# RpiPaw1_Sch.net
KiCad netlist of a schematic drawn in Altium Designer
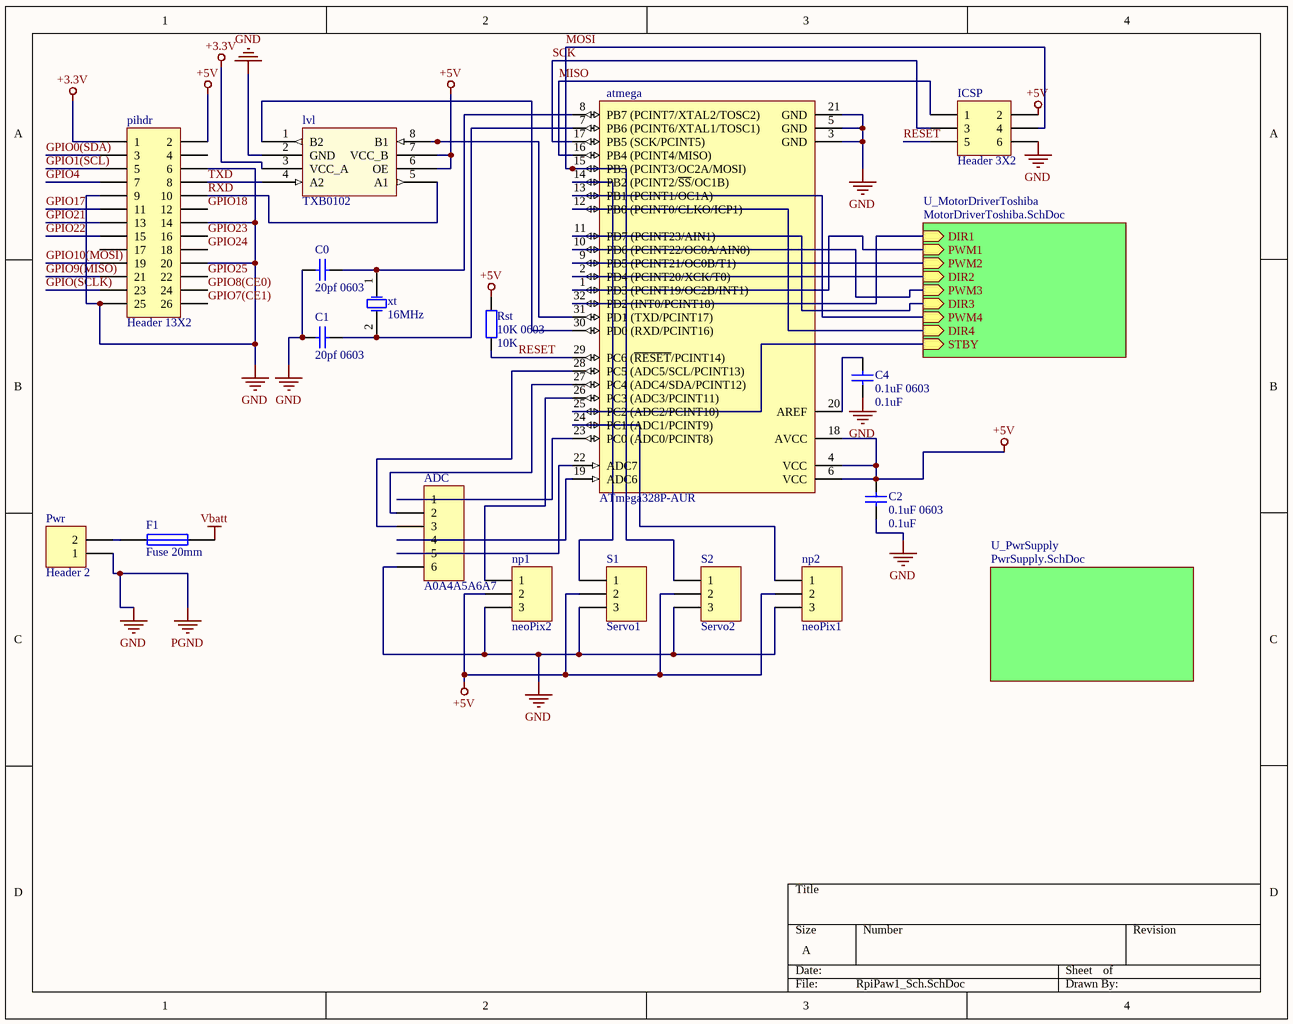
[diagram p0: RpiPaw1_Sch.SchDoc]

(export (version "E")
  (design (tool "Eeschema 10.0.6"))
  (components
    (comp (ref "ADC")
      (value "A0A4A5A6A7")
      (footprint "HDR1X6")
      (description "Header, 6-Pin")
      (fields (field (name "PUBLISHER") "Altium Limited"))
      (libsource (lib "Miscellaneous Connectors") (part "Header 6"))
    )
    (comp (ref "atmega")
      (value "ATmega328P-AUR")
      (footprint "Altera Footprints:TQFP32_N")
      (fields (field (name "PUBLISHER") "Altium Limited"))
      (libsource (lib "Atmel Microcontroller 8-Bit megaAVR") (part "ATmega328P-AUR"))
    )
    (comp (ref "C0")
      (value "20pf 0603")
      (footprint "Miscellaneous Devices:J1-0603")
      (description "Capacitor")
      (fields (field (name "PUBLISHER") "Altium Limited"))
      (libsource (lib "Miscellaneous Devices") (part "Cap"))
    )
    (comp (ref "C1")
      (value "20pf 0603")
      (footprint "Miscellaneous Devices:J1-0603")
      (description "Capacitor")
      (fields (field (name "PUBLISHER") "Altium Limited"))
      (libsource (lib "Miscellaneous Devices") (part "Cap"))
    )
    (comp (ref "C2")
      (value "0.1uF 0603")
      (footprint "Miscellaneous Devices:J1-0603")
      (description "Capacitor")
      (fields (field (name "ALTIUM_VALUE") "0.1uF") (field (name "PUBLISHER") "Altium Limited"))
      (libsource (lib "Miscellaneous Devices") (part "Cap"))
    )
    (comp (ref "C4")
      (value "0.1uF 0603")
      (footprint "J1-0603")
      (description "Capacitor")
      (fields (field (name "ALTIUM_VALUE") "0.1uF") (field (name "PUBLISHER") "Altium Limited"))
      (libsource (lib "Miscellaneous Devices") (part "Cap"))
    )
    (comp (ref "F1")
      (value "Fuse 20mm")
      (footprint "PawPcbLib1:FusePad1")
      (description "Fuse")
      (fields (field (name "PUBLISHER") "Altium Limited"))
      (libsource (lib "Miscellaneous Devices") (part "Fuse 1"))
    )
    (comp (ref "ICSP")
      (value "Header 3X2")
      (footprint "HDR2X3")
      (description "Header, 3-Pin, Dual row")
      (fields (field (name "PUBLISHER") "Altium Limited"))
      (libsource (lib "Miscellaneous Connectors") (part "Header 3X2"))
    )
    (comp (ref "lvl")
      (value "TXB0102")
      (footprint "PawPcbLib1:TSSOP50P310X90-8N")
      (description "3.3V Level translator")
      (libsource (lib "RpiPaw1_SchLib") (part "TXB0102"))
    )
    (comp (ref "np1")
      (value "neoPix2")
      (footprint "HDR1X3")
      (description "Header, 3-Pin")
      (fields (field (name "PUBLISHER") "Altium Limited"))
      (libsource (lib "Miscellaneous Connectors") (part "Header 3"))
    )
    (comp (ref "np2")
      (value "neoPix1")
      (footprint "HDR1X3")
      (description "Header, 3-Pin")
      (fields (field (name "PUBLISHER") "Altium Limited"))
      (libsource (lib "Miscellaneous Connectors") (part "Header 3"))
    )
    (comp (ref "pihdr")
      (value "Header 13X2")
      (footprint "HDR2X13")
      (description "Header, 13-Pin, Dual row")
      (fields (field (name "PUBLISHER") "Altium Limited"))
      (libsource (lib "Miscellaneous Connectors") (part "Header 13X2"))
    )
    (comp (ref "Pwr")
      (value "Header 2")
      (footprint "PawPcbLib1:PwrPlug1")
      (description "Header, 2-Pin")
      (fields (field (name "PUBLISHER") "Altium Limited"))
      (libsource (lib "Miscellaneous Connectors") (part "Header 2"))
    )
    (comp (ref "Rst")
      (value "10K 0603")
      (footprint "J1-0603")
      (description "Resistor")
      (fields (field (name "ALTIUM_VALUE") "10K") (field (name "PUBLISHER") "Altium Limited"))
      (libsource (lib "Miscellaneous Devices") (part "Res2"))
    )
    (comp (ref "S1")
      (value "Servo1")
      (footprint "HDR1X3")
      (description "Header, 3-Pin")
      (fields (field (name "PUBLISHER") "Altium Limited"))
      (libsource (lib "Miscellaneous Connectors") (part "Header 3"))
    )
    (comp (ref "S2")
      (value "Servo2")
      (footprint "HDR1X3")
      (description "Header, 3-Pin")
      (fields (field (name "PUBLISHER") "Altium Limited"))
      (libsource (lib "Miscellaneous Connectors") (part "Header 3"))
    )
    (comp (ref "xt")
      (value "16MHz")
      (footprint "Axial 0.2")
      (description "Crystal Oscillator")
      (fields (field (name "PUBLISHER") "Altium Limited"))
      (libsource (lib "Miscellaneous Devices") (part "XTAL"))
    )
  )
  (nets
    (net (code "1") (name "+3.3V") (class "Default")
      (node (ref "lvl") (pin "3") (pinfunction "VCC_A_3") (pintype "power_in"))
      (node (ref "pihdr") (pin "1") (pinfunction "1_1") (pintype "passive"))
    )
    (net (code "2") (name "+5V") (class "Default")
      (node (ref "C2") (pin "2") (pinfunction "2_2") (pintype "passive"))
      (node (ref "ICSP") (pin "2") (pinfunction "2_2") (pintype "passive"))
      (node (ref "Rst") (pin "2") (pinfunction "2_2") (pintype "passive"))
      (node (ref "S1") (pin "2") (pinfunction "2_2") (pintype "passive"))
      (node (ref "S2") (pin "2") (pinfunction "2_2") (pintype "passive"))
      (node (ref "atmega") (pin "18") (pinfunction "AVCC_18") (pintype "power_in"))
      (node (ref "atmega") (pin "4") (pinfunction "VCC_4") (pintype "power_in"))
      (node (ref "atmega") (pin "6") (pinfunction "VCC_6") (pintype "power_in"))
      (node (ref "lvl") (pin "6") (pinfunction "OE_6") (pintype "passive"))
      (node (ref "lvl") (pin "7") (pinfunction "VCC_B_7") (pintype "power_in"))
      (node (ref "np1") (pin "2") (pinfunction "2_2") (pintype "passive"))
      (node (ref "np2") (pin "2") (pinfunction "2_2") (pintype "passive"))
      (node (ref "pihdr") (pin "2") (pinfunction "2_2") (pintype "passive"))
    )
    (net (code "3") (name "/DIR1") (class "Default")
      (node (ref "atmega") (pin "32") (pinfunction "PD2_(INT0/PCINT18)_32") (pintype "bidirectional"))
    )
    (net (code "4") (name "/DIR2") (class "Default")
      (node (ref "atmega") (pin "2") (pinfunction "PD4_(PCINT20/XCK/T0)_2") (pintype "bidirectional"))
    )
    (net (code "5") (name "/DIR3") (class "Default")
      (node (ref "atmega") (pin "11") (pinfunction "PD7_(PCINT23/AIN1)_11") (pintype "bidirectional"))
    )
    (net (code "6") (name "/DIR4") (class "Default")
      (node (ref "atmega") (pin "12") (pinfunction "PB0_(PCINT0/CLKO/ICP1)_12") (pintype "bidirectional"))
    )
    (net (code "7") (name "/GPIO(SCLK)") (class "Default")
      (node (ref "pihdr") (pin "23") (pinfunction "23_23") (pintype "passive"))
    )
    (net (code "8") (name "/GPIO0(SDA)") (class "Default")
      (node (ref "pihdr") (pin "3") (pinfunction "3_3") (pintype "passive"))
    )
    (net (code "9") (name "/GPIO1(SCL)") (class "Default")
      (node (ref "pihdr") (pin "5") (pinfunction "5_5") (pintype "passive"))
    )
    (net (code "10") (name "/GPIO4") (class "Default")
      (node (ref "pihdr") (pin "7") (pinfunction "7_7") (pintype "passive"))
    )
    (net (code "11") (name "/GPIO7(CE1)") (class "Default")
      (node (ref "pihdr") (pin "26") (pinfunction "26_26") (pintype "passive"))
    )
    (net (code "12") (name "/GPIO8(CE0)") (class "Default")
      (node (ref "pihdr") (pin "24") (pinfunction "24_24") (pintype "passive"))
    )
    (net (code "13") (name "/GPIO9(MISO)") (class "Default")
      (node (ref "pihdr") (pin "21") (pinfunction "21_21") (pintype "passive"))
    )
    (net (code "14") (name "/GPIO10(MOSI)") (class "Default")
      (node (ref "pihdr") (pin "19") (pinfunction "19_19") (pintype "passive"))
    )
    (net (code "15") (name "/GPIO17") (class "Default")
      (node (ref "pihdr") (pin "11") (pinfunction "11_11") (pintype "passive"))
    )
    (net (code "16") (name "/GPIO18") (class "Default")
      (node (ref "pihdr") (pin "12") (pinfunction "12_12") (pintype "passive"))
    )
    (net (code "17") (name "/GPIO21") (class "Default")
      (node (ref "pihdr") (pin "13") (pinfunction "13_13") (pintype "passive"))
    )
    (net (code "18") (name "/GPIO22") (class "Default")
      (node (ref "pihdr") (pin "15") (pinfunction "15_15") (pintype "passive"))
    )
    (net (code "19") (name "/GPIO23") (class "Default")
      (node (ref "pihdr") (pin "16") (pinfunction "16_16") (pintype "passive"))
    )
    (net (code "20") (name "/GPIO24") (class "Default")
      (node (ref "pihdr") (pin "18") (pinfunction "18_18") (pintype "passive"))
    )
    (net (code "21") (name "/GPIO25") (class "Default")
      (node (ref "pihdr") (pin "22") (pinfunction "22_22") (pintype "passive"))
    )
    (net (code "22") (name "/MISO") (class "Default")
      (node (ref "ICSP") (pin "1") (pinfunction "1_1") (pintype "passive"))
      (node (ref "atmega") (pin "16") (pinfunction "PB4_(PCINT4/MISO)_16") (pintype "bidirectional"))
    )
    (net (code "23") (name "/MOSI") (class "Default")
      (node (ref "ICSP") (pin "4") (pinfunction "4_4") (pintype "passive"))
      (node (ref "S2") (pin "1") (pinfunction "1_1") (pintype "passive"))
      (node (ref "atmega") (pin "15") (pinfunction "PB3_(PCINT3/OC2A/MOSI)_15") (pintype "bidirectional"))
    )
    (net (code "24") (name "/PWM1") (class "Default")
      (node (ref "atmega") (pin "1") (pinfunction "PD3_(PCINT19/OC2B/INT1)_1") (pintype "bidirectional"))
    )
    (net (code "25") (name "/PWM2") (class "Default")
      (node (ref "atmega") (pin "9") (pinfunction "PD5_(PCINT21/OC0B/T1)_9") (pintype "bidirectional"))
    )
    (net (code "26") (name "/PWM3") (class "Default")
      (node (ref "atmega") (pin "10") (pinfunction "PD6_(PCINT22/OC0A/AIN0)_10") (pintype "bidirectional"))
    )
    (net (code "27") (name "/PWM4") (class "Default")
      (node (ref "atmega") (pin "13") (pinfunction "PB1_(PCINT1/OC1A)_13") (pintype "bidirectional"))
    )
    (net (code "28") (name "/RESET") (class "Default")
      (node (ref "ICSP") (pin "5") (pinfunction "5_5") (pintype "passive"))
      (node (ref "Rst") (pin "1") (pinfunction "1_1") (pintype "passive"))
      (node (ref "atmega") (pin "29") (pinfunction "PC6_(~{RESET}/PCINT14)_29") (pintype "bidirectional"))
    )
    (net (code "29") (name "/RXD") (class "Default")
      (node (ref "lvl") (pin "5") (pinfunction "A1_5") (pintype "output"))
      (node (ref "pihdr") (pin "10") (pinfunction "10_10") (pintype "passive"))
    )
    (net (code "30") (name "/SCK") (class "Default")
      (node (ref "ICSP") (pin "3") (pinfunction "3_3") (pintype "passive"))
      (node (ref "atmega") (pin "17") (pinfunction "PB5_(SCK/PCINT5)_17") (pintype "bidirectional"))
    )
    (net (code "31") (name "/STBY") (class "Default")
      (node (ref "atmega") (pin "25") (pinfunction "PC2_(ADC2/PCINT10)_25") (pintype "bidirectional"))
    )
    (net (code "32") (name "/TXD") (class "Default")
      (node (ref "lvl") (pin "4") (pinfunction "A2_4") (pintype "input"))
      (node (ref "pihdr") (pin "8") (pinfunction "8_8") (pintype "passive"))
    )
    (net (code "33") (name "GND") (class "Default")
      (node (ref "ADC") (pin "6") (pinfunction "6_6") (pintype "passive"))
      (node (ref "C0") (pin "1") (pinfunction "1_1") (pintype "passive"))
      (node (ref "C1") (pin "1") (pinfunction "1_1") (pintype "passive"))
      (node (ref "C2") (pin "1") (pinfunction "1_1") (pintype "passive"))
      (node (ref "C4") (pin "1") (pinfunction "1_1") (pintype "passive"))
      (node (ref "ICSP") (pin "6") (pinfunction "6_6") (pintype "passive"))
      (node (ref "Pwr") (pin "1") (pinfunction "1_1") (pintype "passive"))
      (node (ref "S1") (pin "3") (pinfunction "3_3") (pintype "passive"))
      (node (ref "S2") (pin "3") (pinfunction "3_3") (pintype "passive"))
      (node (ref "atmega") (pin "21") (pinfunction "GND_21") (pintype "power_in"))
      (node (ref "atmega") (pin "3") (pinfunction "GND_3") (pintype "power_in"))
      (node (ref "atmega") (pin "5") (pinfunction "GND_5") (pintype "power_in"))
      (node (ref "lvl") (pin "2") (pinfunction "GND_2") (pintype "power_in"))
      (node (ref "np1") (pin "3") (pinfunction "3_3") (pintype "passive"))
      (node (ref "np2") (pin "3") (pinfunction "3_3") (pintype "passive"))
      (node (ref "pihdr") (pin "14") (pinfunction "14_14") (pintype "passive"))
      (node (ref "pihdr") (pin "20") (pinfunction "20_20") (pintype "passive"))
      (node (ref "pihdr") (pin "25") (pinfunction "25_25") (pintype "passive"))
      (node (ref "pihdr") (pin "6") (pinfunction "6_6") (pintype "passive"))
      (node (ref "pihdr") (pin "9") (pinfunction "9_9") (pintype "passive"))
    )
    (net (code "34") (name "Net-(F1-Pad1)") (class "Default")
      (node (ref "F1") (pin "1") (pinfunction "1_1") (pintype "passive"))
      (node (ref "Pwr") (pin "2") (pinfunction "2_2") (pintype "passive"))
    )
    (net (code "35") (name "Net-(atmega-ADC6)") (class "Default")
      (node (ref "ADC") (pin "4") (pinfunction "4_4") (pintype "passive"))
      (node (ref "atmega") (pin "19") (pinfunction "ADC6_19") (pintype "input"))
    )
    (net (code "36") (name "Net-(atmega-ADC7)") (class "Default")
      (node (ref "ADC") (pin "5") (pinfunction "5_5") (pintype "passive"))
      (node (ref "atmega") (pin "22") (pinfunction "ADC7_22") (pintype "input"))
    )
    (net (code "37") (name "Net-(atmega-AREF)") (class "Default")
      (node (ref "C4") (pin "2") (pinfunction "2_2") (pintype "passive"))
      (node (ref "atmega") (pin "20") (pinfunction "AREF_20") (pintype "passive"))
    )
    (net (code "38") (name "Net-(atmega-PB2_(PCINT2{slash}~{SS}{slash}OC1B))") (class "Default")
      (node (ref "S1") (pin "1") (pinfunction "1_1") (pintype "passive"))
      (node (ref "atmega") (pin "14") (pinfunction "PB2_(PCINT2/~{SS}/OC1B)_14") (pintype "bidirectional"))
    )
    (net (code "39") (name "Net-(atmega-PB6_(PCINT6{slash}XTAL1{slash}TOSC1))") (class "Default")
      (node (ref "C1") (pin "2") (pinfunction "2_2") (pintype "passive"))
      (node (ref "atmega") (pin "7") (pinfunction "PB6_(PCINT6/XTAL1/TOSC1)_7") (pintype "bidirectional"))
      (node (ref "xt") (pin "2") (pinfunction "OSC2_2") (pintype "passive"))
    )
    (net (code "40") (name "Net-(atmega-PB7_(PCINT7{slash}XTAL2{slash}TOSC2))") (class "Default")
      (node (ref "C0") (pin "2") (pinfunction "2_2") (pintype "passive"))
      (node (ref "atmega") (pin "8") (pinfunction "PB7_(PCINT7/XTAL2/TOSC2)_8") (pintype "bidirectional"))
      (node (ref "xt") (pin "1") (pinfunction "OSC1_1") (pintype "passive"))
    )
    (net (code "41") (name "Net-(atmega-PC0_(ADC0{slash}PCINT8))") (class "Default")
      (node (ref "ADC") (pin "1") (pinfunction "1_1") (pintype "passive"))
      (node (ref "atmega") (pin "23") (pinfunction "PC0_(ADC0/PCINT8)_23") (pintype "bidirectional"))
    )
    (net (code "42") (name "Net-(atmega-PC1_(ADC1{slash}PCINT9))") (class "Default")
      (node (ref "atmega") (pin "24") (pinfunction "PC1_(ADC1/PCINT9)_24") (pintype "bidirectional"))
      (node (ref "np2") (pin "1") (pinfunction "1_1") (pintype "passive"))
    )
    (net (code "43") (name "Net-(atmega-PC3_(ADC3{slash}PCINT11))") (class "Default")
      (node (ref "atmega") (pin "26") (pinfunction "PC3_(ADC3/PCINT11)_26") (pintype "bidirectional"))
      (node (ref "np1") (pin "1") (pinfunction "1_1") (pintype "passive"))
    )
    (net (code "44") (name "Net-(atmega-PC4_(ADC4{slash}SDA{slash}PCINT12))") (class "Default")
      (node (ref "ADC") (pin "2") (pinfunction "2_2") (pintype "passive"))
      (node (ref "atmega") (pin "27") (pinfunction "PC4_(ADC4/SDA/PCINT12)_27") (pintype "bidirectional"))
    )
    (net (code "45") (name "Net-(atmega-PC5_(ADC5{slash}SCL{slash}PCINT13))") (class "Default")
      (node (ref "ADC") (pin "3") (pinfunction "3_3") (pintype "passive"))
      (node (ref "atmega") (pin "28") (pinfunction "PC5_(ADC5/SCL/PCINT13)_28") (pintype "bidirectional"))
    )
    (net (code "46") (name "Net-(atmega-PD0_(RXD{slash}PCINT16))") (class "Default")
      (node (ref "atmega") (pin "30") (pinfunction "PD0_(RXD/PCINT16)_30") (pintype "bidirectional"))
      (node (ref "lvl") (pin "1") (pinfunction "B2_1") (pintype "output"))
    )
    (net (code "47") (name "Net-(atmega-PD1_(TXD{slash}PCINT17))") (class "Default")
      (node (ref "atmega") (pin "31") (pinfunction "PD1_(TXD/PCINT17)_31") (pintype "bidirectional"))
      (node (ref "lvl") (pin "8") (pinfunction "B1_8") (pintype "input"))
    )
    (net (code "48") (name "Vbatt") (class "Default")
      (node (ref "F1") (pin "2") (pinfunction "2_2") (pintype "passive"))
    )
    (net (code "49") (name "unconnected-(pihdr-Pad4)") (class "Default")
      (node (ref "pihdr") (pin "4") (pinfunction "4_4") (pintype "passive"))
    )
    (net (code "50") (name "unconnected-(pihdr-Pad17)") (class "Default")
      (node (ref "pihdr") (pin "17") (pinfunction "17_17") (pintype "passive"))
    )
  )
)
